# date2-shift-r1.net
KiCad netlist of a schematic drawn in EAGLE
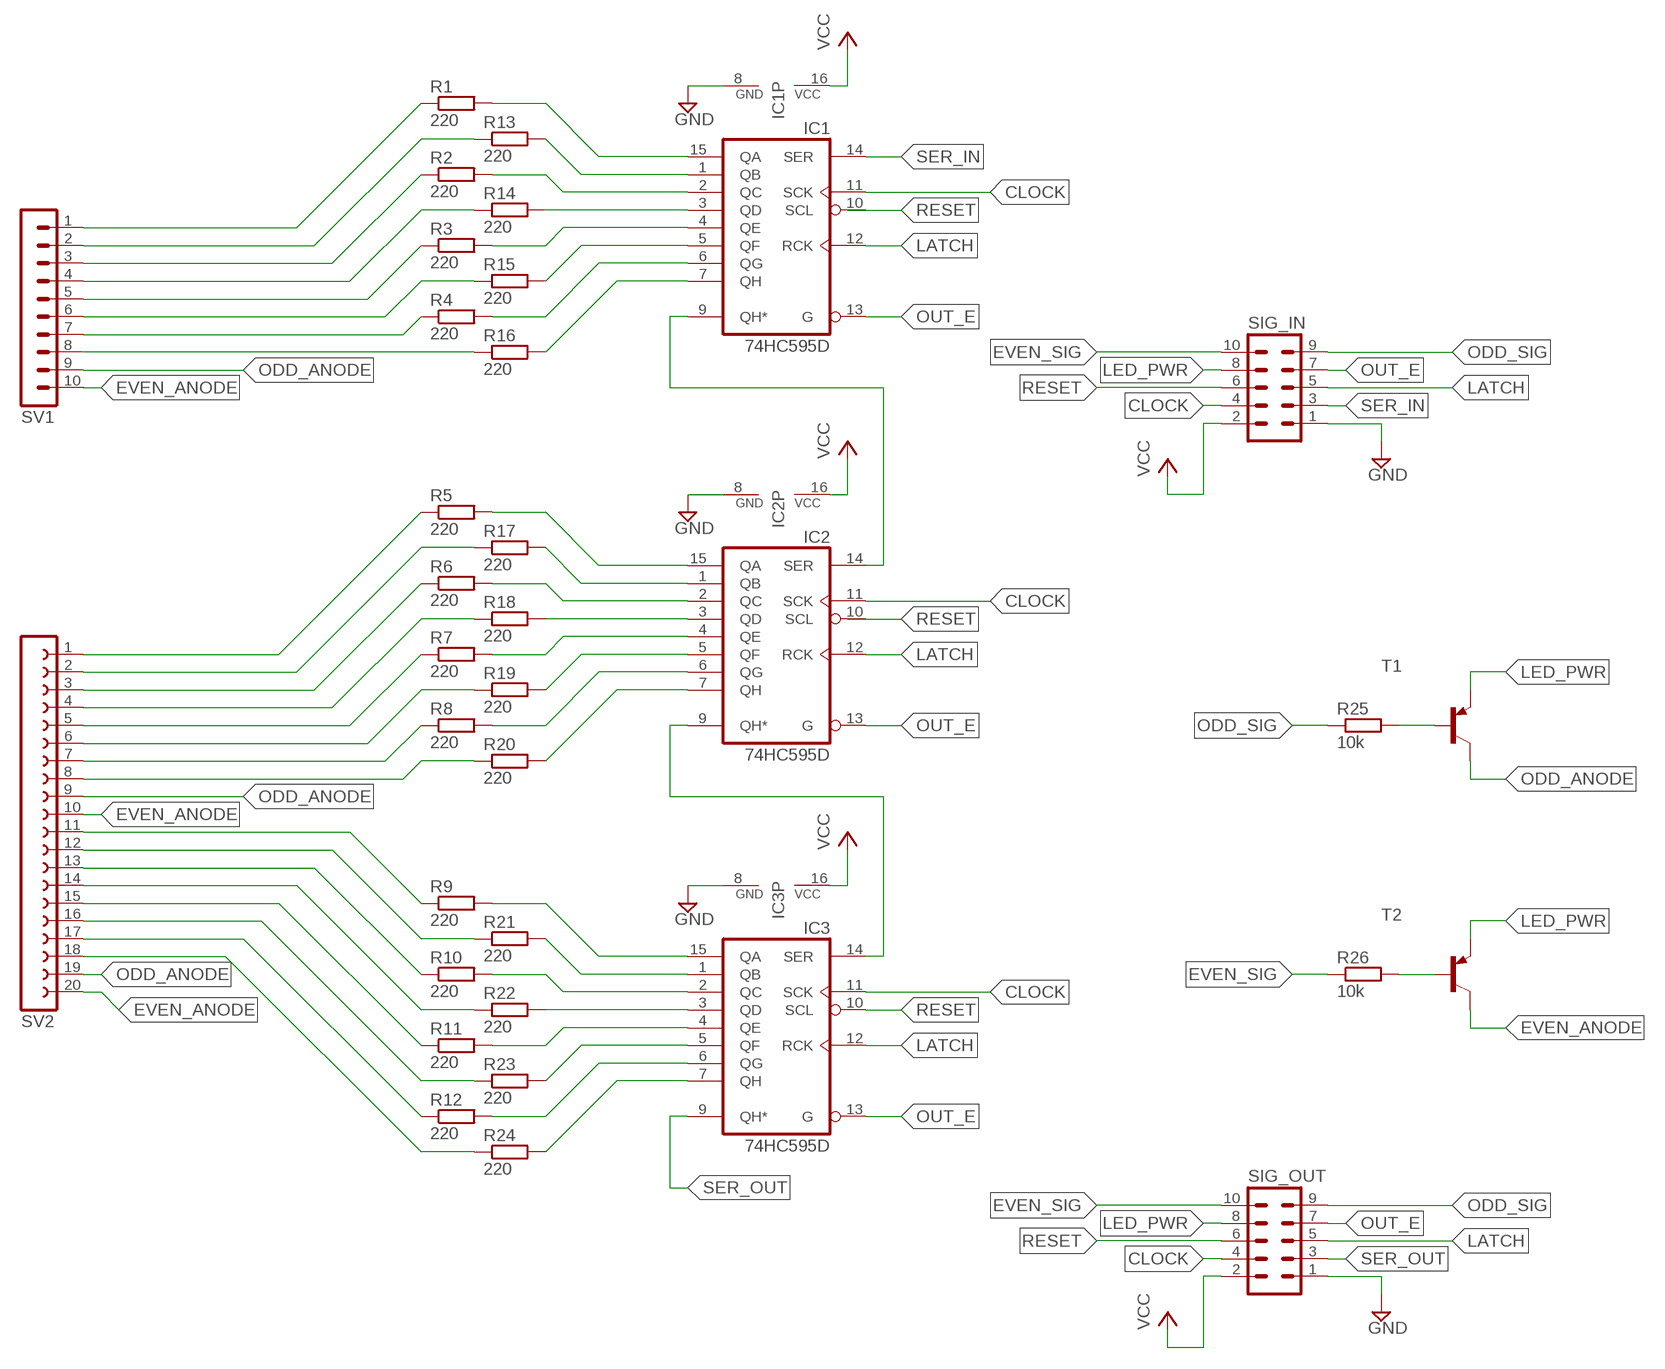
[diagram p0: schematic, sheet 1]

(export (version "E")
  (design (tool "Eeschema 10.0.6"))
  (components
    (comp (ref "IC1")
      (value "74HC595D")
      (footprint "eagle-import:SO16")
      (libsource (lib "eagle-import") (part "74595DHC"))
    )
    (comp (ref "IC2")
      (value "74HC595D")
      (footprint "eagle-import:SO16")
      (libsource (lib "eagle-import") (part "74595DHC"))
    )
    (comp (ref "IC3")
      (value "74HC595D")
      (footprint "eagle-import:SO16")
      (libsource (lib "eagle-import") (part "74595DHC"))
    )
    (comp (ref "R1")
      (value "220")
      (footprint "eagle-import:R0805")
      (libsource (lib "eagle-import") (part "R-EU_R0805"))
    )
    (comp (ref "R2")
      (value "220")
      (footprint "eagle-import:R0805")
      (libsource (lib "eagle-import") (part "R-EU_R0805"))
    )
    (comp (ref "R3")
      (value "220")
      (footprint "eagle-import:R0805")
      (libsource (lib "eagle-import") (part "R-EU_R0805"))
    )
    (comp (ref "R4")
      (value "220")
      (footprint "eagle-import:R0805")
      (libsource (lib "eagle-import") (part "R-EU_R0805"))
    )
    (comp (ref "R5")
      (value "220")
      (footprint "eagle-import:R0805")
      (libsource (lib "eagle-import") (part "R-EU_R0805"))
    )
    (comp (ref "R6")
      (value "220")
      (footprint "eagle-import:R0805")
      (libsource (lib "eagle-import") (part "R-EU_R0805"))
    )
    (comp (ref "R7")
      (value "220")
      (footprint "eagle-import:R0805")
      (libsource (lib "eagle-import") (part "R-EU_R0805"))
    )
    (comp (ref "R8")
      (value "220")
      (footprint "eagle-import:R0805")
      (libsource (lib "eagle-import") (part "R-EU_R0805"))
    )
    (comp (ref "R9")
      (value "220")
      (footprint "eagle-import:R0805")
      (libsource (lib "eagle-import") (part "R-EU_R0805"))
    )
    (comp (ref "R10")
      (value "220")
      (footprint "eagle-import:R0805")
      (libsource (lib "eagle-import") (part "R-EU_R0805"))
    )
    (comp (ref "R11")
      (value "220")
      (footprint "eagle-import:R0805")
      (libsource (lib "eagle-import") (part "R-EU_R0805"))
    )
    (comp (ref "R12")
      (value "220")
      (footprint "eagle-import:R0805")
      (libsource (lib "eagle-import") (part "R-EU_R0805"))
    )
    (comp (ref "R13")
      (value "220")
      (footprint "eagle-import:R0805")
      (libsource (lib "eagle-import") (part "R-EU_R0805"))
    )
    (comp (ref "R14")
      (value "220")
      (footprint "eagle-import:R0805")
      (libsource (lib "eagle-import") (part "R-EU_R0805"))
    )
    (comp (ref "R15")
      (value "220")
      (footprint "eagle-import:R0805")
      (libsource (lib "eagle-import") (part "R-EU_R0805"))
    )
    (comp (ref "R16")
      (value "220")
      (footprint "eagle-import:R0805")
      (libsource (lib "eagle-import") (part "R-EU_R0805"))
    )
    (comp (ref "R17")
      (value "220")
      (footprint "eagle-import:R0805")
      (libsource (lib "eagle-import") (part "R-EU_R0805"))
    )
    (comp (ref "R18")
      (value "220")
      (footprint "eagle-import:R0805")
      (libsource (lib "eagle-import") (part "R-EU_R0805"))
    )
    (comp (ref "R19")
      (value "220")
      (footprint "eagle-import:R0805")
      (libsource (lib "eagle-import") (part "R-EU_R0805"))
    )
    (comp (ref "R20")
      (value "220")
      (footprint "eagle-import:R0805")
      (libsource (lib "eagle-import") (part "R-EU_R0805"))
    )
    (comp (ref "R21")
      (value "220")
      (footprint "eagle-import:R0805")
      (libsource (lib "eagle-import") (part "R-EU_R0805"))
    )
    (comp (ref "R22")
      (value "220")
      (footprint "eagle-import:R0805")
      (libsource (lib "eagle-import") (part "R-EU_R0805"))
    )
    (comp (ref "R23")
      (value "220")
      (footprint "eagle-import:R0805")
      (libsource (lib "eagle-import") (part "R-EU_R0805"))
    )
    (comp (ref "R24")
      (value "220")
      (footprint "eagle-import:R0805")
      (libsource (lib "eagle-import") (part "R-EU_R0805"))
    )
    (comp (ref "R25")
      (value "10k")
      (footprint "eagle-import:R0805")
      (libsource (lib "eagle-import") (part "R-EU_R0805"))
    )
    (comp (ref "R26")
      (value "10k")
      (footprint "eagle-import:R0805")
      (libsource (lib "eagle-import") (part "R-EU_R0805"))
    )
    (comp (ref "SIG_IN")
      (value "MA05-2")
      (footprint "eagle-import:MA05-2")
      (libsource (lib "eagle-import") (part "MA05-2"))
    )
    (comp (ref "SIG_OUT")
      (value "MA05-2")
      (footprint "eagle-import:MA05-2")
      (libsource (lib "eagle-import") (part "MA05-2"))
    )
    (comp (ref "SV1")
      (value "MA10-1")
      (footprint "eagle-import:MA10-1")
      (libsource (lib "eagle-import") (part "MA10-1"))
    )
    (comp (ref "SV2")
      (value "FE20-1")
      (footprint "eagle-import:FE20")
      (libsource (lib "eagle-import") (part "FE20-1"))
    )
    (comp (ref "T1")
      (value "BC557B-PNP-TO92-EBC")
      (footprint "eagle-import:TO92-EBC")
      (libsource (lib "eagle-import") (part "-PNP-TO92-EBCBC557B"))
    )
    (comp (ref "T2")
      (value "BC557B-PNP-TO92-EBC")
      (footprint "eagle-import:TO92-EBC")
      (libsource (lib "eagle-import") (part "-PNP-TO92-EBCBC557B"))
    )
  )
  (nets
    (net (code "1") (name "CLOCK") (class "Default")
      (node (ref "IC1") (pin "11") (pinfunction "SCK_11") (pintype "input"))
      (node (ref "IC2") (pin "11") (pinfunction "SCK_11") (pintype "input"))
      (node (ref "IC3") (pin "11") (pinfunction "SCK_11") (pintype "input"))
      (node (ref "SIG_IN") (pin "4") (pinfunction "4_4") (pintype "passive"))
      (node (ref "SIG_OUT") (pin "4") (pinfunction "4_4") (pintype "passive"))
    )
    (net (code "2") (name "EVEN_ANODE") (class "Default")
      (node (ref "SV1") (pin "10") (pinfunction "10_10") (pintype "passive"))
      (node (ref "SV2") (pin "10") (pinfunction "10_10") (pintype "passive"))
      (node (ref "SV2") (pin "20") (pinfunction "20_20") (pintype "passive"))
      (node (ref "T2") (pin "C") (pinfunction "C_C") (pintype "passive"))
    )
    (net (code "3") (name "EVEN_SIG") (class "Default")
      (node (ref "R26") (pin "1") (pinfunction "1_1") (pintype "passive"))
      (node (ref "SIG_IN") (pin "10") (pinfunction "10_10") (pintype "passive"))
      (node (ref "SIG_OUT") (pin "10") (pinfunction "10_10") (pintype "passive"))
    )
    (net (code "4") (name "GND") (class "Default")
      (node (ref "IC1") (pin "8") (pinfunction "GND_8") (pintype "power_in"))
      (node (ref "IC2") (pin "8") (pinfunction "GND_8") (pintype "power_in"))
      (node (ref "IC3") (pin "8") (pinfunction "GND_8") (pintype "power_in"))
      (node (ref "SIG_IN") (pin "1") (pinfunction "1_1") (pintype "passive"))
      (node (ref "SIG_OUT") (pin "1") (pinfunction "1_1") (pintype "passive"))
    )
    (net (code "5") (name "LATCH") (class "Default")
      (node (ref "IC1") (pin "12") (pinfunction "RCK_12") (pintype "input"))
      (node (ref "IC2") (pin "12") (pinfunction "RCK_12") (pintype "input"))
      (node (ref "IC3") (pin "12") (pinfunction "RCK_12") (pintype "input"))
      (node (ref "SIG_IN") (pin "5") (pinfunction "5_5") (pintype "passive"))
      (node (ref "SIG_OUT") (pin "5") (pinfunction "5_5") (pintype "passive"))
    )
    (net (code "6") (name "LED_PWR") (class "Default")
      (node (ref "SIG_IN") (pin "8") (pinfunction "8_8") (pintype "passive"))
      (node (ref "SIG_OUT") (pin "8") (pinfunction "8_8") (pintype "passive"))
      (node (ref "T1") (pin "E") (pinfunction "E_E") (pintype "passive"))
      (node (ref "T2") (pin "E") (pinfunction "E_E") (pintype "passive"))
    )
    (net (code "7") (name "Net-(IC1A-QA)") (class "Default")
      (node (ref "IC1") (pin "15") (pinfunction "QA_15") (pintype "tri_state"))
      (node (ref "R1") (pin "2") (pinfunction "2_2") (pintype "passive"))
    )
    (net (code "8") (name "Net-(IC1A-QB)") (class "Default")
      (node (ref "IC1") (pin "1") (pinfunction "QB_1") (pintype "tri_state"))
      (node (ref "R13") (pin "2") (pinfunction "2_2") (pintype "passive"))
    )
    (net (code "9") (name "Net-(IC1A-QC)") (class "Default")
      (node (ref "IC1") (pin "2") (pinfunction "QC_2") (pintype "tri_state"))
      (node (ref "R2") (pin "2") (pinfunction "2_2") (pintype "passive"))
    )
    (net (code "10") (name "Net-(IC1A-QD)") (class "Default")
      (node (ref "IC1") (pin "3") (pinfunction "QD_3") (pintype "tri_state"))
      (node (ref "R14") (pin "2") (pinfunction "2_2") (pintype "passive"))
    )
    (net (code "11") (name "Net-(IC1A-QE)") (class "Default")
      (node (ref "IC1") (pin "4") (pinfunction "QE_4") (pintype "tri_state"))
      (node (ref "R3") (pin "2") (pinfunction "2_2") (pintype "passive"))
    )
    (net (code "12") (name "Net-(IC1A-QF)") (class "Default")
      (node (ref "IC1") (pin "5") (pinfunction "QF_5") (pintype "tri_state"))
      (node (ref "R15") (pin "2") (pinfunction "2_2") (pintype "passive"))
    )
    (net (code "13") (name "Net-(IC1A-QG)") (class "Default")
      (node (ref "IC1") (pin "6") (pinfunction "QG_6") (pintype "tri_state"))
      (node (ref "R4") (pin "2") (pinfunction "2_2") (pintype "passive"))
    )
    (net (code "14") (name "Net-(IC1A-QH)") (class "Default")
      (node (ref "IC1") (pin "7") (pinfunction "QH_7") (pintype "tri_state"))
      (node (ref "R16") (pin "2") (pinfunction "2_2") (pintype "passive"))
    )
    (net (code "15") (name "Net-(IC1A-QH*)") (class "Default")
      (node (ref "IC1") (pin "9") (pinfunction "QH*_9") (pintype "tri_state"))
      (node (ref "IC2") (pin "14") (pinfunction "SER_14") (pintype "input"))
    )
    (net (code "16") (name "Net-(IC2A-QA)") (class "Default")
      (node (ref "IC2") (pin "15") (pinfunction "QA_15") (pintype "tri_state"))
      (node (ref "R5") (pin "2") (pinfunction "2_2") (pintype "passive"))
    )
    (net (code "17") (name "Net-(IC2A-QB)") (class "Default")
      (node (ref "IC2") (pin "1") (pinfunction "QB_1") (pintype "tri_state"))
      (node (ref "R17") (pin "2") (pinfunction "2_2") (pintype "passive"))
    )
    (net (code "18") (name "Net-(IC2A-QC)") (class "Default")
      (node (ref "IC2") (pin "2") (pinfunction "QC_2") (pintype "tri_state"))
      (node (ref "R6") (pin "2") (pinfunction "2_2") (pintype "passive"))
    )
    (net (code "19") (name "Net-(IC2A-QD)") (class "Default")
      (node (ref "IC2") (pin "3") (pinfunction "QD_3") (pintype "tri_state"))
      (node (ref "R18") (pin "2") (pinfunction "2_2") (pintype "passive"))
    )
    (net (code "20") (name "Net-(IC2A-QE)") (class "Default")
      (node (ref "IC2") (pin "4") (pinfunction "QE_4") (pintype "tri_state"))
      (node (ref "R7") (pin "2") (pinfunction "2_2") (pintype "passive"))
    )
    (net (code "21") (name "Net-(IC2A-QF)") (class "Default")
      (node (ref "IC2") (pin "5") (pinfunction "QF_5") (pintype "tri_state"))
      (node (ref "R19") (pin "2") (pinfunction "2_2") (pintype "passive"))
    )
    (net (code "22") (name "Net-(IC2A-QG)") (class "Default")
      (node (ref "IC2") (pin "6") (pinfunction "QG_6") (pintype "tri_state"))
      (node (ref "R8") (pin "2") (pinfunction "2_2") (pintype "passive"))
    )
    (net (code "23") (name "Net-(IC2A-QH)") (class "Default")
      (node (ref "IC2") (pin "7") (pinfunction "QH_7") (pintype "tri_state"))
      (node (ref "R20") (pin "2") (pinfunction "2_2") (pintype "passive"))
    )
    (net (code "24") (name "Net-(IC2A-QH*)") (class "Default")
      (node (ref "IC2") (pin "9") (pinfunction "QH*_9") (pintype "tri_state"))
      (node (ref "IC3") (pin "14") (pinfunction "SER_14") (pintype "input"))
    )
    (net (code "25") (name "Net-(IC3A-QA)") (class "Default")
      (node (ref "IC3") (pin "15") (pinfunction "QA_15") (pintype "tri_state"))
      (node (ref "R9") (pin "2") (pinfunction "2_2") (pintype "passive"))
    )
    (net (code "26") (name "Net-(IC3A-QB)") (class "Default")
      (node (ref "IC3") (pin "1") (pinfunction "QB_1") (pintype "tri_state"))
      (node (ref "R21") (pin "2") (pinfunction "2_2") (pintype "passive"))
    )
    (net (code "27") (name "Net-(IC3A-QC)") (class "Default")
      (node (ref "IC3") (pin "2") (pinfunction "QC_2") (pintype "tri_state"))
      (node (ref "R10") (pin "2") (pinfunction "2_2") (pintype "passive"))
    )
    (net (code "28") (name "Net-(IC3A-QD)") (class "Default")
      (node (ref "IC3") (pin "3") (pinfunction "QD_3") (pintype "tri_state"))
      (node (ref "R22") (pin "2") (pinfunction "2_2") (pintype "passive"))
    )
    (net (code "29") (name "Net-(IC3A-QE)") (class "Default")
      (node (ref "IC3") (pin "4") (pinfunction "QE_4") (pintype "tri_state"))
      (node (ref "R11") (pin "2") (pinfunction "2_2") (pintype "passive"))
    )
    (net (code "30") (name "Net-(IC3A-QF)") (class "Default")
      (node (ref "IC3") (pin "5") (pinfunction "QF_5") (pintype "tri_state"))
      (node (ref "R23") (pin "2") (pinfunction "2_2") (pintype "passive"))
    )
    (net (code "31") (name "Net-(IC3A-QG)") (class "Default")
      (node (ref "IC3") (pin "6") (pinfunction "QG_6") (pintype "tri_state"))
      (node (ref "R12") (pin "2") (pinfunction "2_2") (pintype "passive"))
    )
    (net (code "32") (name "Net-(IC3A-QH)") (class "Default")
      (node (ref "IC3") (pin "7") (pinfunction "QH_7") (pintype "tri_state"))
      (node (ref "R24") (pin "2") (pinfunction "2_2") (pintype "passive"))
    )
    (net (code "33") (name "Net-(R1-Pad1)") (class "Default")
      (node (ref "R1") (pin "1") (pinfunction "1_1") (pintype "passive"))
      (node (ref "SV1") (pin "1") (pinfunction "1_1") (pintype "passive"))
    )
    (net (code "34") (name "Net-(R2-Pad1)") (class "Default")
      (node (ref "R2") (pin "1") (pinfunction "1_1") (pintype "passive"))
      (node (ref "SV1") (pin "3") (pinfunction "3_3") (pintype "passive"))
    )
    (net (code "35") (name "Net-(R3-Pad1)") (class "Default")
      (node (ref "R3") (pin "1") (pinfunction "1_1") (pintype "passive"))
      (node (ref "SV1") (pin "5") (pinfunction "5_5") (pintype "passive"))
    )
    (net (code "36") (name "Net-(R4-Pad1)") (class "Default")
      (node (ref "R4") (pin "1") (pinfunction "1_1") (pintype "passive"))
      (node (ref "SV1") (pin "7") (pinfunction "7_7") (pintype "passive"))
    )
    (net (code "37") (name "Net-(R5-Pad1)") (class "Default")
      (node (ref "R5") (pin "1") (pinfunction "1_1") (pintype "passive"))
      (node (ref "SV2") (pin "1") (pinfunction "1_1") (pintype "passive"))
    )
    (net (code "38") (name "Net-(R6-Pad1)") (class "Default")
      (node (ref "R6") (pin "1") (pinfunction "1_1") (pintype "passive"))
      (node (ref "SV2") (pin "3") (pinfunction "3_3") (pintype "passive"))
    )
    (net (code "39") (name "Net-(R7-Pad1)") (class "Default")
      (node (ref "R7") (pin "1") (pinfunction "1_1") (pintype "passive"))
      (node (ref "SV2") (pin "5") (pinfunction "5_5") (pintype "passive"))
    )
    (net (code "40") (name "Net-(R8-Pad1)") (class "Default")
      (node (ref "R8") (pin "1") (pinfunction "1_1") (pintype "passive"))
      (node (ref "SV2") (pin "7") (pinfunction "7_7") (pintype "passive"))
    )
    (net (code "41") (name "Net-(R9-Pad1)") (class "Default")
      (node (ref "R9") (pin "1") (pinfunction "1_1") (pintype "passive"))
      (node (ref "SV2") (pin "11") (pinfunction "11_11") (pintype "passive"))
    )
    (net (code "42") (name "Net-(R10-Pad1)") (class "Default")
      (node (ref "R10") (pin "1") (pinfunction "1_1") (pintype "passive"))
      (node (ref "SV2") (pin "13") (pinfunction "13_13") (pintype "passive"))
    )
    (net (code "43") (name "Net-(R11-Pad1)") (class "Default")
      (node (ref "R11") (pin "1") (pinfunction "1_1") (pintype "passive"))
      (node (ref "SV2") (pin "15") (pinfunction "15_15") (pintype "passive"))
    )
    (net (code "44") (name "Net-(R12-Pad1)") (class "Default")
      (node (ref "R12") (pin "1") (pinfunction "1_1") (pintype "passive"))
      (node (ref "SV2") (pin "17") (pinfunction "17_17") (pintype "passive"))
    )
    (net (code "45") (name "Net-(R13-Pad1)") (class "Default")
      (node (ref "R13") (pin "1") (pinfunction "1_1") (pintype "passive"))
      (node (ref "SV1") (pin "2") (pinfunction "2_2") (pintype "passive"))
    )
    (net (code "46") (name "Net-(R14-Pad1)") (class "Default")
      (node (ref "R14") (pin "1") (pinfunction "1_1") (pintype "passive"))
      (node (ref "SV1") (pin "4") (pinfunction "4_4") (pintype "passive"))
    )
    (net (code "47") (name "Net-(R15-Pad1)") (class "Default")
      (node (ref "R15") (pin "1") (pinfunction "1_1") (pintype "passive"))
      (node (ref "SV1") (pin "6") (pinfunction "6_6") (pintype "passive"))
    )
    (net (code "48") (name "Net-(R16-Pad1)") (class "Default")
      (node (ref "R16") (pin "1") (pinfunction "1_1") (pintype "passive"))
      (node (ref "SV1") (pin "8") (pinfunction "8_8") (pintype "passive"))
    )
    (net (code "49") (name "Net-(R17-Pad1)") (class "Default")
      (node (ref "R17") (pin "1") (pinfunction "1_1") (pintype "passive"))
      (node (ref "SV2") (pin "2") (pinfunction "2_2") (pintype "passive"))
    )
    (net (code "50") (name "Net-(R18-Pad1)") (class "Default")
      (node (ref "R18") (pin "1") (pinfunction "1_1") (pintype "passive"))
      (node (ref "SV2") (pin "4") (pinfunction "4_4") (pintype "passive"))
    )
    (net (code "51") (name "Net-(R19-Pad1)") (class "Default")
      (node (ref "R19") (pin "1") (pinfunction "1_1") (pintype "passive"))
      (node (ref "SV2") (pin "6") (pinfunction "6_6") (pintype "passive"))
    )
    (net (code "52") (name "Net-(R20-Pad1)") (class "Default")
      (node (ref "R20") (pin "1") (pinfunction "1_1") (pintype "passive"))
      (node (ref "SV2") (pin "8") (pinfunction "8_8") (pintype "passive"))
    )
    (net (code "53") (name "Net-(R21-Pad1)") (class "Default")
      (node (ref "R21") (pin "1") (pinfunction "1_1") (pintype "passive"))
      (node (ref "SV2") (pin "12") (pinfunction "12_12") (pintype "passive"))
    )
    (net (code "54") (name "Net-(R22-Pad1)") (class "Default")
      (node (ref "R22") (pin "1") (pinfunction "1_1") (pintype "passive"))
      (node (ref "SV2") (pin "14") (pinfunction "14_14") (pintype "passive"))
    )
    (net (code "55") (name "Net-(R23-Pad1)") (class "Default")
      (node (ref "R23") (pin "1") (pinfunction "1_1") (pintype "passive"))
      (node (ref "SV2") (pin "16") (pinfunction "16_16") (pintype "passive"))
    )
    (net (code "56") (name "Net-(R24-Pad1)") (class "Default")
      (node (ref "R24") (pin "1") (pinfunction "1_1") (pintype "passive"))
      (node (ref "SV2") (pin "18") (pinfunction "18_18") (pintype "passive"))
    )
    (net (code "57") (name "Net-(R25-Pad2)") (class "Default")
      (node (ref "R25") (pin "2") (pinfunction "2_2") (pintype "passive"))
      (node (ref "T1") (pin "B") (pinfunction "B_B") (pintype "passive"))
    )
    (net (code "58") (name "Net-(R26-Pad2)") (class "Default")
      (node (ref "R26") (pin "2") (pinfunction "2_2") (pintype "passive"))
      (node (ref "T2") (pin "B") (pinfunction "B_B") (pintype "passive"))
    )
    (net (code "59") (name "ODD_ANODE") (class "Default")
      (node (ref "SV1") (pin "9") (pinfunction "9_9") (pintype "passive"))
      (node (ref "SV2") (pin "19") (pinfunction "19_19") (pintype "passive"))
      (node (ref "SV2") (pin "9") (pinfunction "9_9") (pintype "passive"))
      (node (ref "T1") (pin "C") (pinfunction "C_C") (pintype "passive"))
    )
    (net (code "60") (name "ODD_SIG") (class "Default")
      (node (ref "R25") (pin "1") (pinfunction "1_1") (pintype "passive"))
      (node (ref "SIG_IN") (pin "9") (pinfunction "9_9") (pintype "passive"))
      (node (ref "SIG_OUT") (pin "9") (pinfunction "9_9") (pintype "passive"))
    )
    (net (code "61") (name "OUT_E") (class "Default")
      (node (ref "IC1") (pin "13") (pinfunction "G_13") (pintype "input"))
      (node (ref "IC2") (pin "13") (pinfunction "G_13") (pintype "input"))
      (node (ref "IC3") (pin "13") (pinfunction "G_13") (pintype "input"))
      (node (ref "SIG_IN") (pin "7") (pinfunction "7_7") (pintype "passive"))
      (node (ref "SIG_OUT") (pin "7") (pinfunction "7_7") (pintype "passive"))
    )
    (net (code "62") (name "RESET") (class "Default")
      (node (ref "IC3") (pin "10") (pinfunction "SCL_10") (pintype "input"))
      (node (ref "SIG_IN") (pin "6") (pinfunction "6_6") (pintype "passive"))
      (node (ref "SIG_OUT") (pin "6") (pinfunction "6_6") (pintype "passive"))
    )
    (net (code "63") (name "SER_IN") (class "Default")
      (node (ref "IC1") (pin "14") (pinfunction "SER_14") (pintype "input"))
      (node (ref "SIG_IN") (pin "3") (pinfunction "3_3") (pintype "passive"))
    )
    (net (code "64") (name "SER_OUT") (class "Default")
      (node (ref "IC3") (pin "9") (pinfunction "QH*_9") (pintype "tri_state"))
      (node (ref "SIG_OUT") (pin "3") (pinfunction "3_3") (pintype "passive"))
    )
    (net (code "65") (name "VCC") (class "Default")
      (node (ref "IC1") (pin "16") (pinfunction "VCC_16") (pintype "power_in"))
      (node (ref "IC2") (pin "16") (pinfunction "VCC_16") (pintype "power_in"))
      (node (ref "IC3") (pin "16") (pinfunction "VCC_16") (pintype "power_in"))
      (node (ref "SIG_IN") (pin "2") (pinfunction "2_2") (pintype "passive"))
      (node (ref "SIG_OUT") (pin "2") (pinfunction "2_2") (pintype "passive"))
    )
    (net (code "66") (name "unconnected-(IC1A-SCL-Pad10)") (class "Default")
      (node (ref "IC1") (pin "10") (pinfunction "SCL_10") (pintype "input"))
    )
    (net (code "67") (name "unconnected-(IC2A-SCL-Pad10)") (class "Default")
      (node (ref "IC2") (pin "10") (pinfunction "SCL_10") (pintype "input"))
    )
  )
)
